# VREG_CCU_HAS.net
KiCad netlist of a schematic drawn in Altium Designer
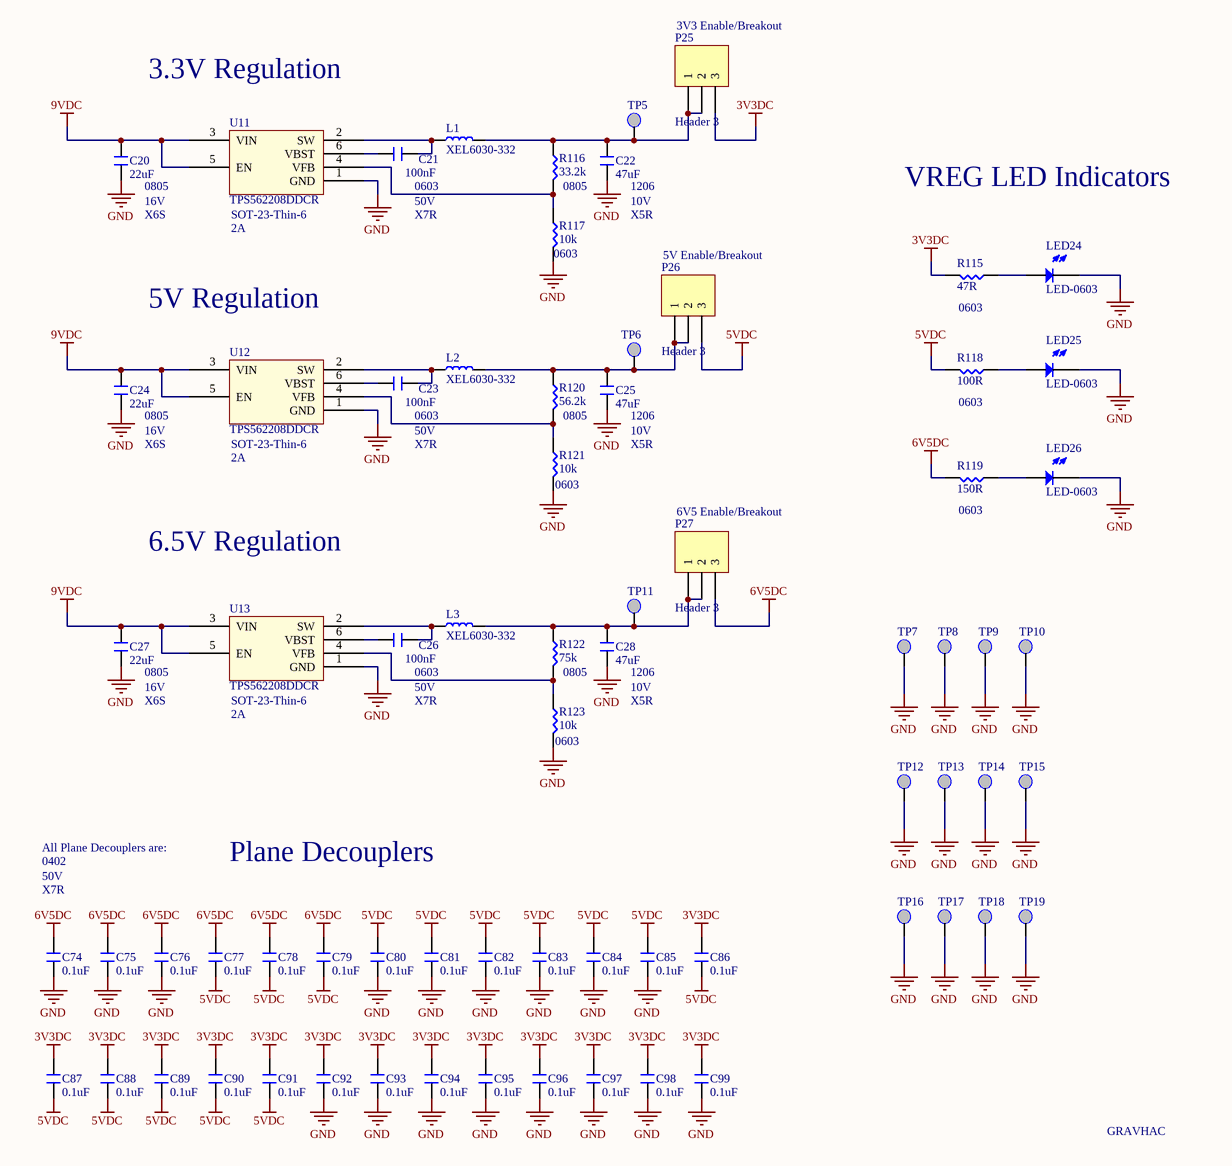
[diagram p0: VREG_CCU_HAS.SchDoc]

(export (version "E")
  (design (tool "Eeschema 10.0.6"))
  (components
    (comp (ref "C20")
      (value "22uF")
      (footprint "NonPolar-0805")
      (libsource (lib "GravLib") (part "Cap - 0805"))
    )
    (comp (ref "C21")
      (value "100nF")
      (footprint "NonPolar-0603")
      (libsource (lib "GravLib") (part "Cap - 0603"))
    )
    (comp (ref "C22")
      (value "47uF")
      (footprint "NONPOLAR-1206")
      (libsource (lib "GravLib") (part "Cap - 1206"))
    )
    (comp (ref "C23")
      (value "100nF")
      (footprint "NonPolar-0603")
      (libsource (lib "GravLib") (part "Cap - 0603"))
    )
    (comp (ref "C24")
      (value "22uF")
      (footprint "NonPolar-0805")
      (libsource (lib "GravLib") (part "Cap - 0805"))
    )
    (comp (ref "C25")
      (value "47uF")
      (footprint "NONPOLAR-1206")
      (libsource (lib "GravLib") (part "Cap - 1206"))
    )
    (comp (ref "C26")
      (value "100nF")
      (footprint "NonPolar-0603")
      (libsource (lib "GravLib") (part "Cap - 0603"))
    )
    (comp (ref "C27")
      (value "22uF")
      (footprint "NonPolar-0805")
      (libsource (lib "GravLib") (part "Cap - 0805"))
    )
    (comp (ref "C28")
      (value "47uF")
      (footprint "NONPOLAR-1206")
      (libsource (lib "GravLib") (part "Cap - 1206"))
    )
    (comp (ref "C74")
      (value "0.1uF")
      (footprint "NonPolar-0402")
      (libsource (lib "GravLib") (part "Cap - 0402"))
    )
    (comp (ref "C75")
      (value "0.1uF")
      (footprint "NonPolar-0402")
      (libsource (lib "GravLib") (part "Cap - 0402"))
    )
    (comp (ref "C76")
      (value "0.1uF")
      (footprint "NonPolar-0402")
      (libsource (lib "GravLib") (part "Cap - 0402"))
    )
    (comp (ref "C77")
      (value "0.1uF")
      (footprint "NonPolar-0402")
      (libsource (lib "GravLib") (part "Cap - 0402"))
    )
    (comp (ref "C78")
      (value "0.1uF")
      (footprint "NonPolar-0402")
      (libsource (lib "GravLib") (part "Cap - 0402"))
    )
    (comp (ref "C79")
      (value "0.1uF")
      (footprint "NonPolar-0402")
      (libsource (lib "GravLib") (part "Cap - 0402"))
    )
    (comp (ref "C80")
      (value "0.1uF")
      (footprint "NonPolar-0402")
      (libsource (lib "GravLib") (part "Cap - 0402"))
    )
    (comp (ref "C81")
      (value "0.1uF")
      (footprint "NonPolar-0402")
      (libsource (lib "GravLib") (part "Cap - 0402"))
    )
    (comp (ref "C82")
      (value "0.1uF")
      (footprint "NonPolar-0402")
      (libsource (lib "GravLib") (part "Cap - 0402"))
    )
    (comp (ref "C83")
      (value "0.1uF")
      (footprint "NonPolar-0402")
      (libsource (lib "GravLib") (part "Cap - 0402"))
    )
    (comp (ref "C84")
      (value "0.1uF")
      (footprint "NonPolar-0402")
      (libsource (lib "GravLib") (part "Cap - 0402"))
    )
    (comp (ref "C85")
      (value "0.1uF")
      (footprint "NonPolar-0402")
      (libsource (lib "GravLib") (part "Cap - 0402"))
    )
    (comp (ref "C86")
      (value "0.1uF")
      (footprint "NonPolar-0402")
      (libsource (lib "GravLib") (part "Cap - 0402"))
    )
    (comp (ref "C87")
      (value "0.1uF")
      (footprint "NonPolar-0402")
      (libsource (lib "GravLib") (part "Cap - 0402"))
    )
    (comp (ref "C88")
      (value "0.1uF")
      (footprint "NonPolar-0402")
      (libsource (lib "GravLib") (part "Cap - 0402"))
    )
    (comp (ref "C89")
      (value "0.1uF")
      (footprint "NonPolar-0402")
      (libsource (lib "GravLib") (part "Cap - 0402"))
    )
    (comp (ref "C90")
      (value "0.1uF")
      (footprint "NonPolar-0402")
      (libsource (lib "GravLib") (part "Cap - 0402"))
    )
    (comp (ref "C91")
      (value "0.1uF")
      (footprint "NonPolar-0402")
      (libsource (lib "GravLib") (part "Cap - 0402"))
    )
    (comp (ref "C92")
      (value "0.1uF")
      (footprint "NonPolar-0402")
      (libsource (lib "GravLib") (part "Cap - 0402"))
    )
    (comp (ref "C93")
      (value "0.1uF")
      (footprint "NonPolar-0402")
      (libsource (lib "GravLib") (part "Cap - 0402"))
    )
    (comp (ref "C94")
      (value "0.1uF")
      (footprint "NonPolar-0402")
      (libsource (lib "GravLib") (part "Cap - 0402"))
    )
    (comp (ref "C95")
      (value "0.1uF")
      (footprint "NonPolar-0402")
      (libsource (lib "GravLib") (part "Cap - 0402"))
    )
    (comp (ref "C96")
      (value "0.1uF")
      (footprint "NonPolar-0402")
      (libsource (lib "GravLib") (part "Cap - 0402"))
    )
    (comp (ref "C97")
      (value "0.1uF")
      (footprint "NonPolar-0402")
      (libsource (lib "GravLib") (part "Cap - 0402"))
    )
    (comp (ref "C98")
      (value "0.1uF")
      (footprint "NonPolar-0402")
      (libsource (lib "GravLib") (part "Cap - 0402"))
    )
    (comp (ref "C99")
      (value "0.1uF")
      (footprint "NonPolar-0402")
      (libsource (lib "GravLib") (part "Cap - 0402"))
    )
    (comp (ref "L1")
      (value "XEL6030-332")
      (footprint "XEL6030-33uH")
      (libsource (lib "GravLib") (part "XEL6030-332"))
    )
    (comp (ref "L2")
      (value "XEL6030-332")
      (footprint "XEL6030-33uH")
      (libsource (lib "GravLib") (part "XEL6030-332"))
    )
    (comp (ref "L3")
      (value "XEL6030-332")
      (footprint "XEL6030-33uH")
      (libsource (lib "GravLib") (part "XEL6030-332"))
    )
    (comp (ref "LED24")
      (value "LED-0603")
      (footprint "LED-0603")
      (libsource (lib "GravLib") (part "LED-0603"))
    )
    (comp (ref "LED25")
      (value "LED-0603")
      (footprint "LED-0603")
      (libsource (lib "GravLib") (part "LED-0603"))
    )
    (comp (ref "LED26")
      (value "LED-0603")
      (footprint "LED-0603")
      (libsource (lib "GravLib") (part "LED-0603"))
    )
    (comp (ref "P25")
      (value "Header 3")
      (footprint "HDR1X3")
      (description "Header, 3-Pin")
      (fields (field (name "PUBLISHER") "Altium Limited"))
      (libsource (lib "Miscellaneous Connectors") (part "Header 3"))
    )
    (comp (ref "P26")
      (value "Header 3")
      (footprint "HDR1X3")
      (description "Header, 3-Pin")
      (fields (field (name "PUBLISHER") "Altium Limited"))
      (libsource (lib "Miscellaneous Connectors") (part "Header 3"))
    )
    (comp (ref "P27")
      (value "Header 3")
      (footprint "HDR1X3")
      (description "Header, 3-Pin")
      (fields (field (name "PUBLISHER") "Altium Limited"))
      (libsource (lib "Miscellaneous Connectors") (part "Header 3"))
    )
    (comp (ref "R115")
      (value "47R")
      (footprint "NonPolar-0603")
      (libsource (lib "GravLib") (part "Res - 0603"))
    )
    (comp (ref "R116")
      (value "33.2k")
      (footprint "NonPolar-0805")
      (libsource (lib "GravLib") (part "Res - 0805"))
    )
    (comp (ref "R117")
      (value "10k")
      (footprint "NonPolar-0603")
      (libsource (lib "GravLib") (part "Res - 0603"))
    )
    (comp (ref "R118")
      (value "100R")
      (footprint "NonPolar-0603")
      (libsource (lib "GravLib") (part "Res - 0603"))
    )
    (comp (ref "R119")
      (value "150R")
      (footprint "NonPolar-0603")
      (libsource (lib "GravLib") (part "Res - 0603"))
    )
    (comp (ref "R120")
      (value "56.2k")
      (footprint "NonPolar-0805")
      (libsource (lib "GravLib") (part "Res - 0805"))
    )
    (comp (ref "R121")
      (value "10k")
      (footprint "NonPolar-0603")
      (libsource (lib "GravLib") (part "Res - 0603"))
    )
    (comp (ref "R122")
      (value "75k")
      (footprint "NonPolar-0805")
      (libsource (lib "GravLib") (part "Res - 0805"))
    )
    (comp (ref "R123")
      (value "10k")
      (footprint "NonPolar-0603")
      (libsource (lib "GravLib") (part "Res - 0603"))
    )
    (comp (ref "TP5")
      (value "TestPoint")
      (footprint "TP - S2751-46R")
      (description "S2751-46R")
      (libsource (lib "GravLib") (part "TestPoint"))
    )
    (comp (ref "TP6")
      (value "TestPoint")
      (footprint "TP - S2751-46R")
      (description "S2751-46R")
      (libsource (lib "GravLib") (part "TestPoint"))
    )
    (comp (ref "TP7")
      (value "TestPoint")
      (footprint "TP - S2751-46R")
      (description "S2751-46R")
      (libsource (lib "GravLib") (part "TestPoint"))
    )
    (comp (ref "TP8")
      (value "TestPoint")
      (footprint "TP - S2751-46R")
      (description "S2751-46R")
      (libsource (lib "GravLib") (part "TestPoint"))
    )
    (comp (ref "TP9")
      (value "TestPoint")
      (footprint "TP - S2751-46R")
      (description "S2751-46R")
      (libsource (lib "GravLib") (part "TestPoint"))
    )
    (comp (ref "TP10")
      (value "TestPoint")
      (footprint "TP - S2751-46R")
      (description "S2751-46R")
      (libsource (lib "GravLib") (part "TestPoint"))
    )
    (comp (ref "TP11")
      (value "TestPoint")
      (footprint "TP - S2751-46R")
      (description "S2751-46R")
      (libsource (lib "GravLib") (part "TestPoint"))
    )
    (comp (ref "TP12")
      (value "TestPoint")
      (footprint "TP - S2751-46R")
      (description "S2751-46R")
      (libsource (lib "GravLib") (part "TestPoint"))
    )
    (comp (ref "TP13")
      (value "TestPoint")
      (footprint "TP - S2751-46R")
      (description "S2751-46R")
      (libsource (lib "GravLib") (part "TestPoint"))
    )
    (comp (ref "TP14")
      (value "TestPoint")
      (footprint "TP - S2751-46R")
      (description "S2751-46R")
      (libsource (lib "GravLib") (part "TestPoint"))
    )
    (comp (ref "TP15")
      (value "TestPoint")
      (footprint "TP - S2751-46R")
      (description "S2751-46R")
      (libsource (lib "GravLib") (part "TestPoint"))
    )
    (comp (ref "TP16")
      (value "TestPoint")
      (footprint "TP - S2751-46R")
      (description "S2751-46R")
      (libsource (lib "GravLib") (part "TestPoint"))
    )
    (comp (ref "TP17")
      (value "TestPoint")
      (footprint "TP - S2751-46R")
      (description "S2751-46R")
      (libsource (lib "GravLib") (part "TestPoint"))
    )
    (comp (ref "TP18")
      (value "TestPoint")
      (footprint "TP - S2751-46R")
      (description "S2751-46R")
      (libsource (lib "GravLib") (part "TestPoint"))
    )
    (comp (ref "TP19")
      (value "TestPoint")
      (footprint "TP - S2751-46R")
      (description "S2751-46R")
      (libsource (lib "GravLib") (part "TestPoint"))
    )
    (comp (ref "U11")
      (value "TPS562208DDCR")
      (footprint "TPS562208DDCR")
      (description "4.5V to 17V Input, 2A Output, Synchronous Step-Down Converter")
      (libsource (lib "GravLib") (part "TPS562208DDCR"))
    )
    (comp (ref "U12")
      (value "TPS562208DDCR")
      (footprint "TPS562208DDCR")
      (description "4.5V to 17V Input, 2A Output, Synchronous Step-Down Converter")
      (libsource (lib "GravLib") (part "TPS562208DDCR"))
    )
    (comp (ref "U13")
      (value "TPS562208DDCR")
      (footprint "TPS562208DDCR")
      (description "4.5V to 17V Input, 2A Output, Synchronous Step-Down Converter")
      (libsource (lib "GravLib") (part "TPS562208DDCR"))
    )
  )
  (nets
    (net (code "1") (name "3V3DC") (class "Default")
      (node (ref "C86") (pin "2") (pinfunction "2_2") (pintype "passive"))
      (node (ref "C87") (pin "2") (pinfunction "2_2") (pintype "passive"))
      (node (ref "C88") (pin "2") (pinfunction "2_2") (pintype "passive"))
      (node (ref "C89") (pin "2") (pinfunction "2_2") (pintype "passive"))
      (node (ref "C90") (pin "2") (pinfunction "2_2") (pintype "passive"))
      (node (ref "C91") (pin "2") (pinfunction "2_2") (pintype "passive"))
      (node (ref "C92") (pin "2") (pinfunction "2_2") (pintype "passive"))
      (node (ref "C93") (pin "2") (pinfunction "2_2") (pintype "passive"))
      (node (ref "C94") (pin "2") (pinfunction "2_2") (pintype "passive"))
      (node (ref "C95") (pin "2") (pinfunction "2_2") (pintype "passive"))
      (node (ref "C96") (pin "2") (pinfunction "2_2") (pintype "passive"))
      (node (ref "C97") (pin "2") (pinfunction "2_2") (pintype "passive"))
      (node (ref "C98") (pin "2") (pinfunction "2_2") (pintype "passive"))
      (node (ref "C99") (pin "2") (pinfunction "2_2") (pintype "passive"))
      (node (ref "P25") (pin "3") (pinfunction "3_3") (pintype "passive"))
      (node (ref "R115") (pin "1") (pinfunction "1_1") (pintype "passive"))
    )
    (net (code "2") (name "5VDC") (class "Default")
      (node (ref "C77") (pin "1") (pinfunction "1_1") (pintype "passive"))
      (node (ref "C78") (pin "1") (pinfunction "1_1") (pintype "passive"))
      (node (ref "C79") (pin "1") (pinfunction "1_1") (pintype "passive"))
      (node (ref "C80") (pin "2") (pinfunction "2_2") (pintype "passive"))
      (node (ref "C81") (pin "2") (pinfunction "2_2") (pintype "passive"))
      (node (ref "C82") (pin "2") (pinfunction "2_2") (pintype "passive"))
      (node (ref "C83") (pin "2") (pinfunction "2_2") (pintype "passive"))
      (node (ref "C84") (pin "2") (pinfunction "2_2") (pintype "passive"))
      (node (ref "C85") (pin "2") (pinfunction "2_2") (pintype "passive"))
      (node (ref "C86") (pin "1") (pinfunction "1_1") (pintype "passive"))
      (node (ref "C87") (pin "1") (pinfunction "1_1") (pintype "passive"))
      (node (ref "C88") (pin "1") (pinfunction "1_1") (pintype "passive"))
      (node (ref "C89") (pin "1") (pinfunction "1_1") (pintype "passive"))
      (node (ref "C90") (pin "1") (pinfunction "1_1") (pintype "passive"))
      (node (ref "C91") (pin "1") (pinfunction "1_1") (pintype "passive"))
      (node (ref "P26") (pin "3") (pinfunction "3_3") (pintype "passive"))
      (node (ref "R118") (pin "1") (pinfunction "1_1") (pintype "passive"))
    )
    (net (code "3") (name "6V5DC") (class "Default")
      (node (ref "C74") (pin "2") (pinfunction "2_2") (pintype "passive"))
      (node (ref "C75") (pin "2") (pinfunction "2_2") (pintype "passive"))
      (node (ref "C76") (pin "2") (pinfunction "2_2") (pintype "passive"))
      (node (ref "C77") (pin "2") (pinfunction "2_2") (pintype "passive"))
      (node (ref "C78") (pin "2") (pinfunction "2_2") (pintype "passive"))
      (node (ref "C79") (pin "2") (pinfunction "2_2") (pintype "passive"))
      (node (ref "P27") (pin "3") (pinfunction "3_3") (pintype "passive"))
      (node (ref "R119") (pin "1") (pinfunction "1_1") (pintype "passive"))
    )
    (net (code "4") (name "9VDC") (class "Default")
      (node (ref "C20") (pin "2") (pinfunction "2_2") (pintype "passive"))
      (node (ref "C24") (pin "2") (pinfunction "2_2") (pintype "passive"))
      (node (ref "C27") (pin "2") (pinfunction "2_2") (pintype "passive"))
      (node (ref "U11") (pin "3") (pinfunction "VIN_3") (pintype "passive"))
      (node (ref "U11") (pin "5") (pinfunction "EN_5") (pintype "passive"))
      (node (ref "U12") (pin "3") (pinfunction "VIN_3") (pintype "passive"))
      (node (ref "U12") (pin "5") (pinfunction "EN_5") (pintype "passive"))
      (node (ref "U13") (pin "3") (pinfunction "VIN_3") (pintype "passive"))
      (node (ref "U13") (pin "5") (pinfunction "EN_5") (pintype "passive"))
    )
    (net (code "5") (name "GND") (class "Default")
      (node (ref "C20") (pin "1") (pinfunction "1_1") (pintype "passive"))
      (node (ref "C22") (pin "1") (pinfunction "1_1") (pintype "passive"))
      (node (ref "C24") (pin "1") (pinfunction "1_1") (pintype "passive"))
      (node (ref "C25") (pin "1") (pinfunction "1_1") (pintype "passive"))
      (node (ref "C27") (pin "1") (pinfunction "1_1") (pintype "passive"))
      (node (ref "C28") (pin "1") (pinfunction "1_1") (pintype "passive"))
      (node (ref "C74") (pin "1") (pinfunction "1_1") (pintype "passive"))
      (node (ref "C75") (pin "1") (pinfunction "1_1") (pintype "passive"))
      (node (ref "C76") (pin "1") (pinfunction "1_1") (pintype "passive"))
      (node (ref "C80") (pin "1") (pinfunction "1_1") (pintype "passive"))
      (node (ref "C81") (pin "1") (pinfunction "1_1") (pintype "passive"))
      (node (ref "C82") (pin "1") (pinfunction "1_1") (pintype "passive"))
      (node (ref "C83") (pin "1") (pinfunction "1_1") (pintype "passive"))
      (node (ref "C84") (pin "1") (pinfunction "1_1") (pintype "passive"))
      (node (ref "C85") (pin "1") (pinfunction "1_1") (pintype "passive"))
      (node (ref "C92") (pin "1") (pinfunction "1_1") (pintype "passive"))
      (node (ref "C93") (pin "1") (pinfunction "1_1") (pintype "passive"))
      (node (ref "C94") (pin "1") (pinfunction "1_1") (pintype "passive"))
      (node (ref "C95") (pin "1") (pinfunction "1_1") (pintype "passive"))
      (node (ref "C96") (pin "1") (pinfunction "1_1") (pintype "passive"))
      (node (ref "C97") (pin "1") (pinfunction "1_1") (pintype "passive"))
      (node (ref "C98") (pin "1") (pinfunction "1_1") (pintype "passive"))
      (node (ref "C99") (pin "1") (pinfunction "1_1") (pintype "passive"))
      (node (ref "LED24") (pin "2") (pinfunction "2_2") (pintype "passive"))
      (node (ref "LED25") (pin "2") (pinfunction "2_2") (pintype "passive"))
      (node (ref "LED26") (pin "2") (pinfunction "2_2") (pintype "passive"))
      (node (ref "R117") (pin "1") (pinfunction "1_1") (pintype "passive"))
      (node (ref "R121") (pin "1") (pinfunction "1_1") (pintype "passive"))
      (node (ref "R123") (pin "1") (pinfunction "1_1") (pintype "passive"))
      (node (ref "TP10") (pin "1") (pinfunction "1_1") (pintype "passive"))
      (node (ref "TP12") (pin "1") (pinfunction "1_1") (pintype "passive"))
      (node (ref "TP13") (pin "1") (pinfunction "1_1") (pintype "passive"))
      (node (ref "TP14") (pin "1") (pinfunction "1_1") (pintype "passive"))
      (node (ref "TP15") (pin "1") (pinfunction "1_1") (pintype "passive"))
      (node (ref "TP16") (pin "1") (pinfunction "1_1") (pintype "passive"))
      (node (ref "TP17") (pin "1") (pinfunction "1_1") (pintype "passive"))
      (node (ref "TP18") (pin "1") (pinfunction "1_1") (pintype "passive"))
      (node (ref "TP19") (pin "1") (pinfunction "1_1") (pintype "passive"))
      (node (ref "TP7") (pin "1") (pinfunction "1_1") (pintype "passive"))
      (node (ref "TP8") (pin "1") (pinfunction "1_1") (pintype "passive"))
      (node (ref "TP9") (pin "1") (pinfunction "1_1") (pintype "passive"))
      (node (ref "U11") (pin "1") (pinfunction "GND_1") (pintype "passive"))
      (node (ref "U12") (pin "1") (pinfunction "GND_1") (pintype "passive"))
      (node (ref "U13") (pin "1") (pinfunction "GND_1") (pintype "passive"))
    )
    (net (code "6") (name "Net-(C22-Pad2)") (class "Default")
      (node (ref "C22") (pin "2") (pinfunction "2_2") (pintype "passive"))
      (node (ref "L1") (pin "2") (pinfunction "2_2") (pintype "passive"))
      (node (ref "P25") (pin "1") (pinfunction "1_1") (pintype "passive"))
      (node (ref "P25") (pin "2") (pinfunction "2_2") (pintype "passive"))
      (node (ref "R116") (pin "2") (pinfunction "2_2") (pintype "passive"))
      (node (ref "TP5") (pin "1") (pinfunction "1_1") (pintype "passive"))
    )
    (net (code "7") (name "Net-(C25-Pad2)") (class "Default")
      (node (ref "C25") (pin "2") (pinfunction "2_2") (pintype "passive"))
      (node (ref "L2") (pin "2") (pinfunction "2_2") (pintype "passive"))
      (node (ref "P26") (pin "1") (pinfunction "1_1") (pintype "passive"))
      (node (ref "P26") (pin "2") (pinfunction "2_2") (pintype "passive"))
      (node (ref "R120") (pin "2") (pinfunction "2_2") (pintype "passive"))
      (node (ref "TP6") (pin "1") (pinfunction "1_1") (pintype "passive"))
    )
    (net (code "8") (name "Net-(C28-Pad2)") (class "Default")
      (node (ref "C28") (pin "2") (pinfunction "2_2") (pintype "passive"))
      (node (ref "L3") (pin "2") (pinfunction "2_2") (pintype "passive"))
      (node (ref "P27") (pin "1") (pinfunction "1_1") (pintype "passive"))
      (node (ref "P27") (pin "2") (pinfunction "2_2") (pintype "passive"))
      (node (ref "R122") (pin "2") (pinfunction "2_2") (pintype "passive"))
      (node (ref "TP11") (pin "1") (pinfunction "1_1") (pintype "passive"))
    )
    (net (code "9") (name "Net-(LED24-Pad1)") (class "Default")
      (node (ref "LED24") (pin "1") (pinfunction "1_1") (pintype "passive"))
      (node (ref "R115") (pin "2") (pinfunction "2_2") (pintype "passive"))
    )
    (net (code "10") (name "Net-(LED25-Pad1)") (class "Default")
      (node (ref "LED25") (pin "1") (pinfunction "1_1") (pintype "passive"))
      (node (ref "R118") (pin "2") (pinfunction "2_2") (pintype "passive"))
    )
    (net (code "11") (name "Net-(LED26-Pad1)") (class "Default")
      (node (ref "LED26") (pin "1") (pinfunction "1_1") (pintype "passive"))
      (node (ref "R119") (pin "2") (pinfunction "2_2") (pintype "passive"))
    )
    (net (code "12") (name "Net-(U11-SW)") (class "Default")
      (node (ref "C21") (pin "2") (pinfunction "2_2") (pintype "passive"))
      (node (ref "L1") (pin "1") (pinfunction "1_1") (pintype "passive"))
      (node (ref "U11") (pin "2") (pinfunction "SW_2") (pintype "passive"))
    )
    (net (code "13") (name "Net-(U11-VBST)") (class "Default")
      (node (ref "C21") (pin "1") (pinfunction "1_1") (pintype "passive"))
      (node (ref "U11") (pin "6") (pinfunction "VBST_6") (pintype "passive"))
    )
    (net (code "14") (name "Net-(U11-VFB)") (class "Default")
      (node (ref "R116") (pin "1") (pinfunction "1_1") (pintype "passive"))
      (node (ref "R117") (pin "2") (pinfunction "2_2") (pintype "passive"))
      (node (ref "U11") (pin "4") (pinfunction "VFB_4") (pintype "passive"))
    )
    (net (code "15") (name "Net-(U12-SW)") (class "Default")
      (node (ref "C23") (pin "2") (pinfunction "2_2") (pintype "passive"))
      (node (ref "L2") (pin "1") (pinfunction "1_1") (pintype "passive"))
      (node (ref "U12") (pin "2") (pinfunction "SW_2") (pintype "passive"))
    )
    (net (code "16") (name "Net-(U12-VBST)") (class "Default")
      (node (ref "C23") (pin "1") (pinfunction "1_1") (pintype "passive"))
      (node (ref "U12") (pin "6") (pinfunction "VBST_6") (pintype "passive"))
    )
    (net (code "17") (name "Net-(U12-VFB)") (class "Default")
      (node (ref "R120") (pin "1") (pinfunction "1_1") (pintype "passive"))
      (node (ref "R121") (pin "2") (pinfunction "2_2") (pintype "passive"))
      (node (ref "U12") (pin "4") (pinfunction "VFB_4") (pintype "passive"))
    )
    (net (code "18") (name "Net-(U13-SW)") (class "Default")
      (node (ref "C26") (pin "2") (pinfunction "2_2") (pintype "passive"))
      (node (ref "L3") (pin "1") (pinfunction "1_1") (pintype "passive"))
      (node (ref "U13") (pin "2") (pinfunction "SW_2") (pintype "passive"))
    )
    (net (code "19") (name "Net-(U13-VBST)") (class "Default")
      (node (ref "C26") (pin "1") (pinfunction "1_1") (pintype "passive"))
      (node (ref "U13") (pin "6") (pinfunction "VBST_6") (pintype "passive"))
    )
    (net (code "20") (name "Net-(U13-VFB)") (class "Default")
      (node (ref "R122") (pin "1") (pinfunction "1_1") (pintype "passive"))
      (node (ref "R123") (pin "2") (pinfunction "2_2") (pintype "passive"))
      (node (ref "U13") (pin "4") (pinfunction "VFB_4") (pintype "passive"))
    )
  )
)
